# 1-Schematic_Robot_Dog_ESP32_Control_PCB_.net
KiCad netlist of a schematic drawn in EasyEDA
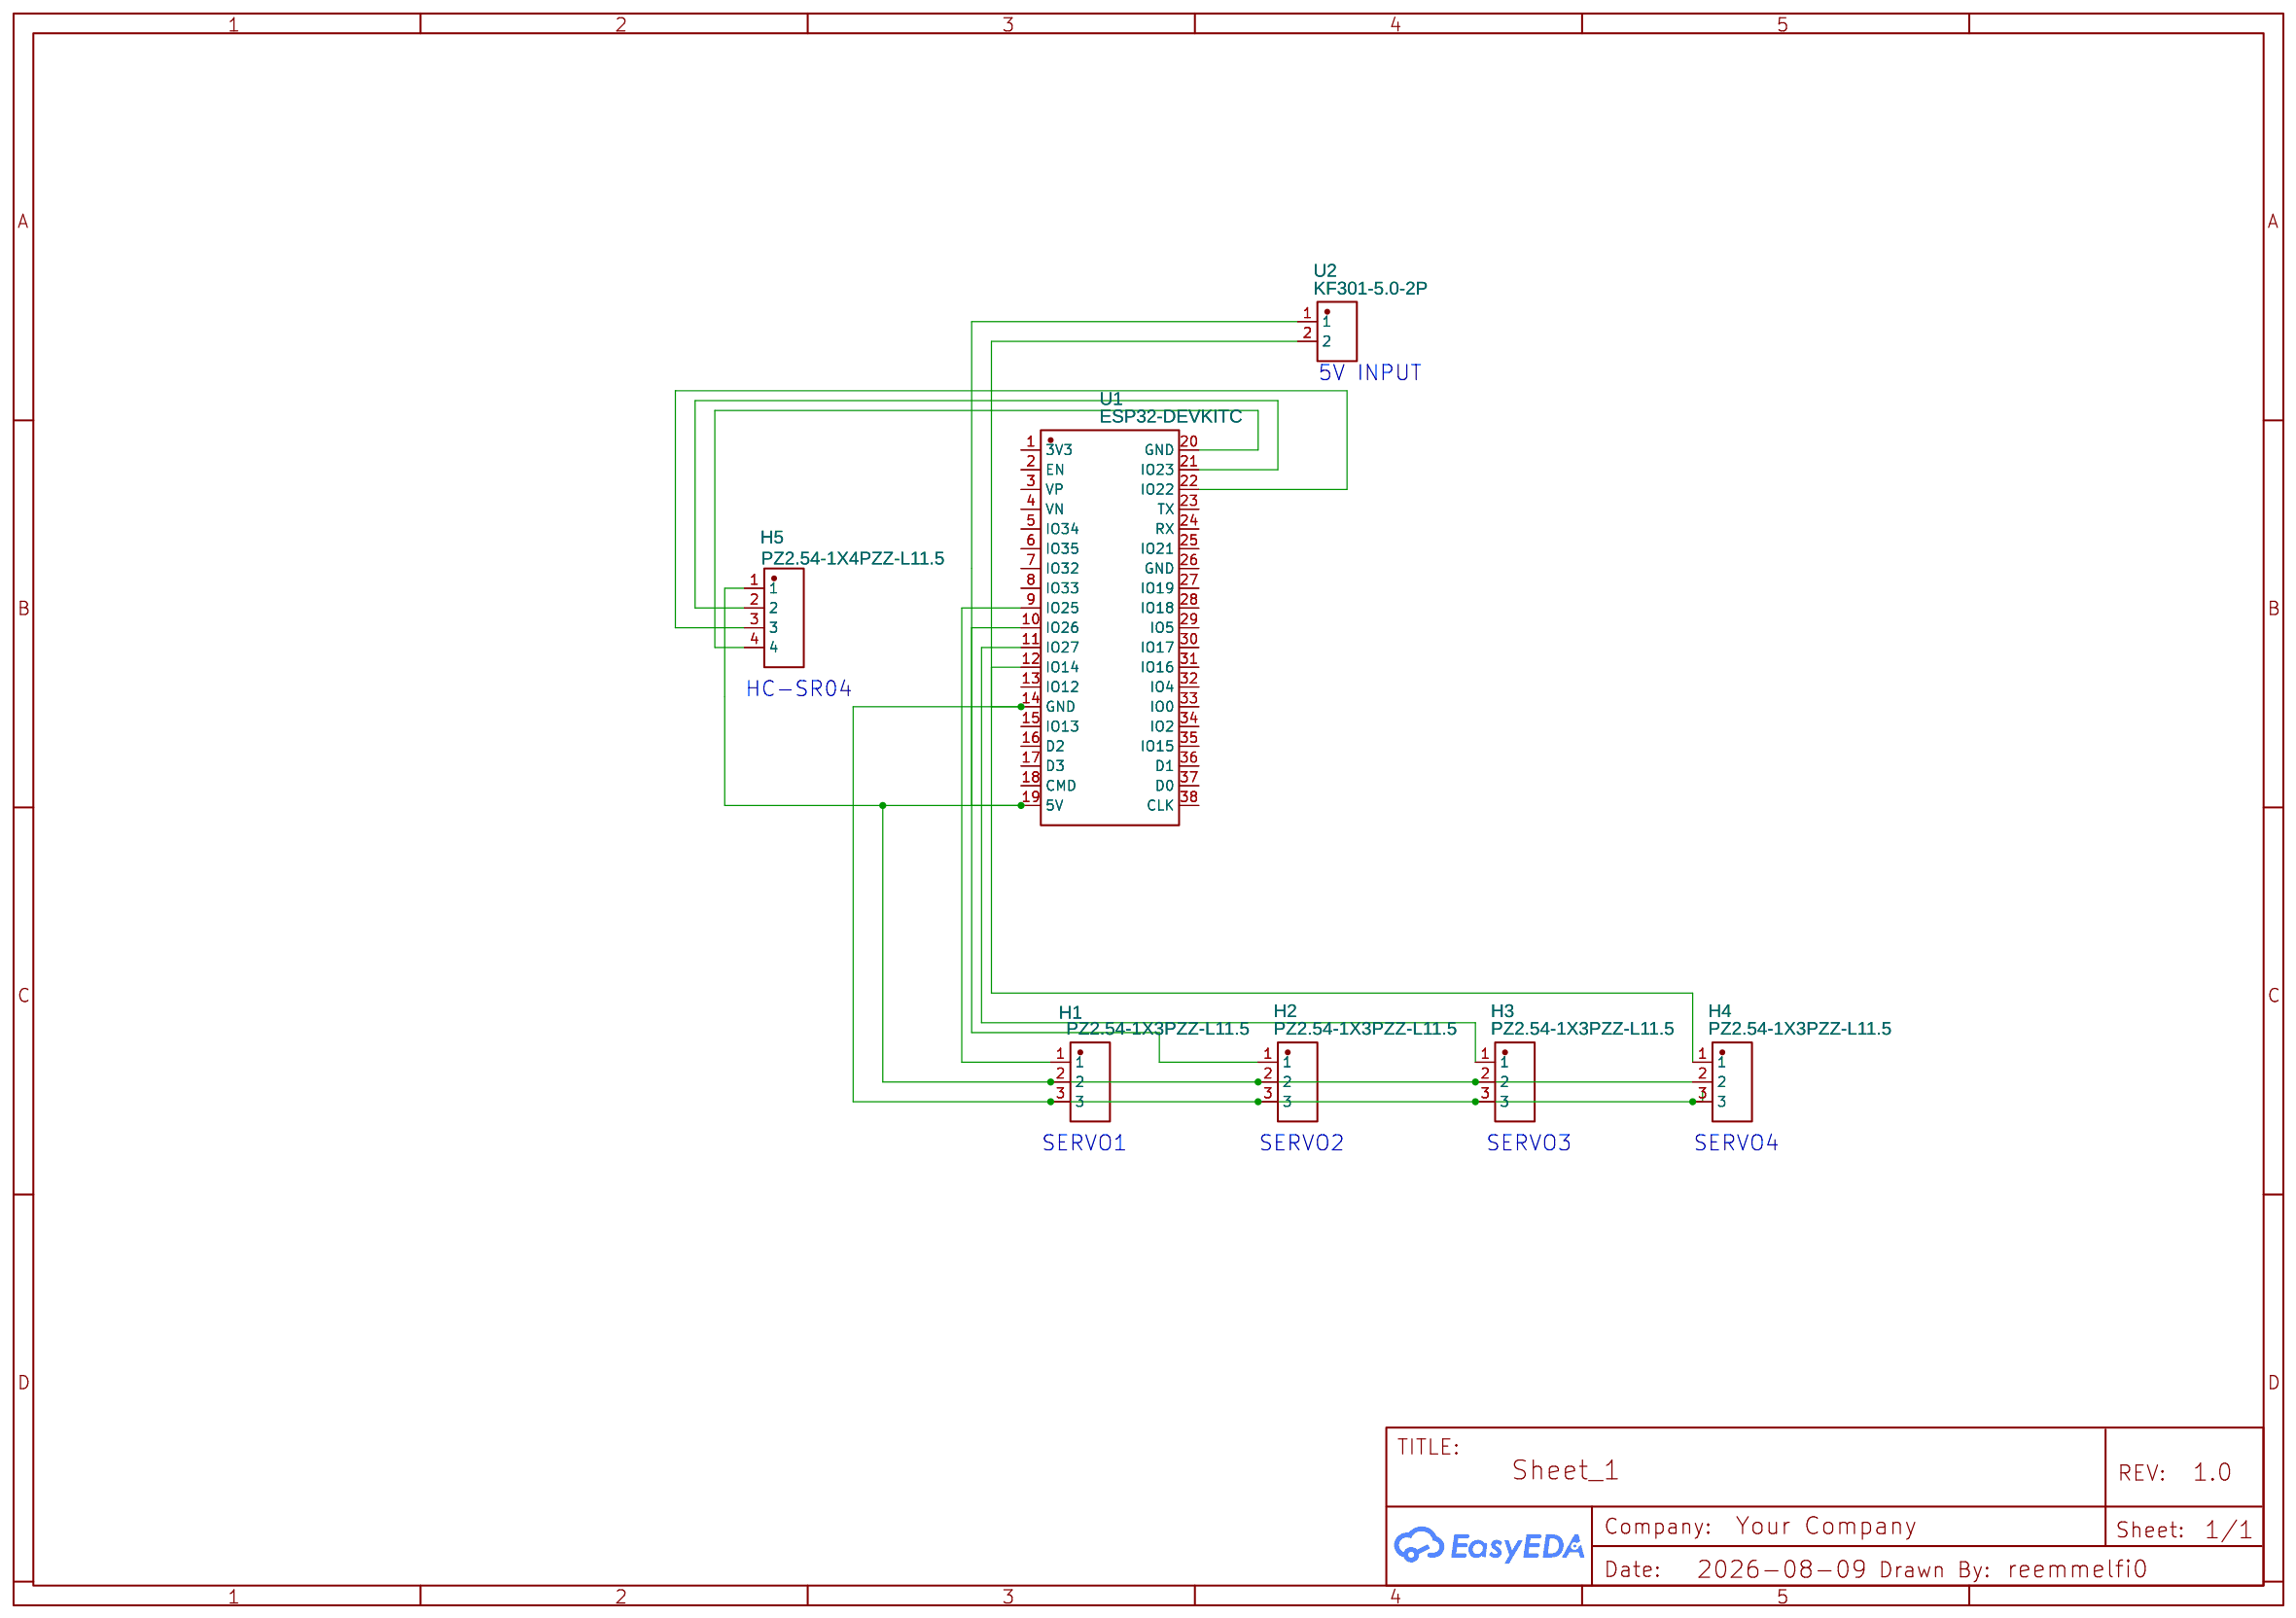
[diagram p0: schematic sheet]

(export (version "E")
  (design (tool "Eeschema 10.0.6"))
  (components
    (comp (ref "H1")
      (value "PZ2.54-1X3PZZ-L11.5")
      (fields
        (field (name "Manufacturer Part") "PZ2.54-1x3PZZ-L11.5")
        (field (name "Manufacturer") "SHOU HAN(首韩)")
      )
      (libsource (lib "") (part "PZ2.54-1X3PZZ-L11.5"))
    )
    (comp (ref "H2")
      (value "PZ2.54-1X3PZZ-L11.5")
      (fields
        (field (name "Manufacturer Part") "PZ2.54-1x3PZZ-L11.5")
        (field (name "Manufacturer") "SHOU HAN(首韩)")
      )
      (libsource (lib "") (part "PZ2.54-1X3PZZ-L11.5"))
    )
    (comp (ref "H3")
      (value "PZ2.54-1X3PZZ-L11.5")
      (fields
        (field (name "Manufacturer Part") "PZ2.54-1x3PZZ-L11.5")
        (field (name "Manufacturer") "SHOU HAN(首韩)")
      )
      (libsource (lib "") (part "PZ2.54-1X3PZZ-L11.5"))
    )
    (comp (ref "H4")
      (value "PZ2.54-1X3PZZ-L11.5")
      (fields
        (field (name "Manufacturer Part") "PZ2.54-1x3PZZ-L11.5")
        (field (name "Manufacturer") "SHOU HAN(首韩)")
      )
      (libsource (lib "") (part "PZ2.54-1X3PZZ-L11.5"))
    )
    (comp (ref "H5")
      (value "PZ2.54-1X4PZZ-L11.5")
      (fields
        (field (name "Manufacturer Part") "PZ2.54-1x4PZZ-L11.5")
        (field (name "Manufacturer") "SHOU HAN(首韩)")
      )
      (libsource (lib "") (part "PZ2.54-1X4PZZ-L11.5"))
    )
    (comp (ref "U1")
      (value "ESP32-DEVKITC")
      (fields
        (field (name "Manufacturer Part") "ESP32-DevKitC")
        (field (name "Manufacturer") "ESPRESSIF(乐鑫)")
      )
      (libsource (lib "") (part "ESP32-DEVKITC"))
    )
    (comp (ref "U2")
      (value "KF301-5.0-2P")
      (fields (field (name "Manufacturer") "KEFA(科发)"))
      (libsource (lib "") (part "KF301-5.0-2P"))
    )
  )
  (nets
    (net (code "1") (name "Net-(H1-Pad3)") (class "Default")
      (node (ref "H1") (pin "3") (pinfunction "3_3") (pintype "unspecified"))
      (node (ref "H2") (pin "3") (pinfunction "3_3") (pintype "unspecified"))
      (node (ref "H3") (pin "3") (pinfunction "3_3") (pintype "unspecified"))
      (node (ref "H4") (pin "3") (pinfunction "3_3") (pintype "unspecified"))
      (node (ref "U1") (pin "14") (pinfunction "GND_14") (pintype "unspecified"))
      (node (ref "U2") (pin "2") (pinfunction "2_2") (pintype "unspecified"))
    )
    (net (code "2") (name "Net-(H5-Pad4)") (class "Default")
      (node (ref "H5") (pin "4") (pinfunction "4_4") (pintype "unspecified"))
      (node (ref "U1") (pin "20") (pinfunction "GND_20") (pintype "unspecified"))
    )
    (net (code "3") (name "Net-(U1-5V)") (class "Default")
      (node (ref "H1") (pin "2") (pinfunction "2_2") (pintype "unspecified"))
      (node (ref "H2") (pin "2") (pinfunction "2_2") (pintype "unspecified"))
      (node (ref "H3") (pin "2") (pinfunction "2_2") (pintype "unspecified"))
      (node (ref "H4") (pin "2") (pinfunction "2_2") (pintype "unspecified"))
      (node (ref "H5") (pin "1") (pinfunction "1_1") (pintype "unspecified"))
      (node (ref "U1") (pin "19") (pinfunction "5V_19") (pintype "unspecified"))
      (node (ref "U2") (pin "1") (pinfunction "1_1") (pintype "unspecified"))
    )
    (net (code "4") (name "Net-(U1-IO14)") (class "Default")
      (node (ref "H4") (pin "1") (pinfunction "1_1") (pintype "unspecified"))
      (node (ref "U1") (pin "12") (pinfunction "IO14_12") (pintype "unspecified"))
    )
    (net (code "5") (name "Net-(U1-IO22)") (class "Default")
      (node (ref "H5") (pin "3") (pinfunction "3_3") (pintype "unspecified"))
      (node (ref "U1") (pin "22") (pinfunction "IO22_22") (pintype "unspecified"))
    )
    (net (code "6") (name "Net-(U1-IO23)") (class "Default")
      (node (ref "H5") (pin "2") (pinfunction "2_2") (pintype "unspecified"))
      (node (ref "U1") (pin "21") (pinfunction "IO23_21") (pintype "unspecified"))
    )
    (net (code "7") (name "Net-(U1-IO25)") (class "Default")
      (node (ref "H1") (pin "1") (pinfunction "1_1") (pintype "unspecified"))
      (node (ref "U1") (pin "9") (pinfunction "IO25_9") (pintype "unspecified"))
    )
    (net (code "8") (name "Net-(U1-IO26)") (class "Default")
      (node (ref "H2") (pin "1") (pinfunction "1_1") (pintype "unspecified"))
      (node (ref "U1") (pin "10") (pinfunction "IO26_10") (pintype "unspecified"))
    )
    (net (code "9") (name "Net-(U1-IO27)") (class "Default")
      (node (ref "H3") (pin "1") (pinfunction "1_1") (pintype "unspecified"))
      (node (ref "U1") (pin "11") (pinfunction "IO27_11") (pintype "unspecified"))
    )
    (net (code "10") (name "unconnected-(U1-3V3-Pad1)") (class "Default")
      (node (ref "U1") (pin "1") (pinfunction "3V3_1") (pintype "unspecified"))
    )
    (net (code "11") (name "unconnected-(U1-CLK-Pad38)") (class "Default")
      (node (ref "U1") (pin "38") (pinfunction "CLK_38") (pintype "unspecified"))
    )
    (net (code "12") (name "unconnected-(U1-CMD-Pad18)") (class "Default")
      (node (ref "U1") (pin "18") (pinfunction "CMD_18") (pintype "unspecified"))
    )
    (net (code "13") (name "unconnected-(U1-D0-Pad37)") (class "Default")
      (node (ref "U1") (pin "37") (pinfunction "D0_37") (pintype "unspecified"))
    )
    (net (code "14") (name "unconnected-(U1-D1-Pad36)") (class "Default")
      (node (ref "U1") (pin "36") (pinfunction "D1_36") (pintype "unspecified"))
    )
    (net (code "15") (name "unconnected-(U1-D2-Pad16)") (class "Default")
      (node (ref "U1") (pin "16") (pinfunction "D2_16") (pintype "unspecified"))
    )
    (net (code "16") (name "unconnected-(U1-D3-Pad17)") (class "Default")
      (node (ref "U1") (pin "17") (pinfunction "D3_17") (pintype "unspecified"))
    )
    (net (code "17") (name "unconnected-(U1-EN-Pad2)") (class "Default")
      (node (ref "U1") (pin "2") (pinfunction "EN_2") (pintype "unspecified"))
    )
    (net (code "18") (name "unconnected-(U1-GND-Pad26)") (class "Default")
      (node (ref "U1") (pin "26") (pinfunction "GND_26") (pintype "unspecified"))
    )
    (net (code "19") (name "unconnected-(U1-IO0-Pad33)") (class "Default")
      (node (ref "U1") (pin "33") (pinfunction "IO0_33") (pintype "unspecified"))
    )
    (net (code "20") (name "unconnected-(U1-IO2-Pad34)") (class "Default")
      (node (ref "U1") (pin "34") (pinfunction "IO2_34") (pintype "unspecified"))
    )
    (net (code "21") (name "unconnected-(U1-IO4-Pad32)") (class "Default")
      (node (ref "U1") (pin "32") (pinfunction "IO4_32") (pintype "unspecified"))
    )
    (net (code "22") (name "unconnected-(U1-IO5-Pad29)") (class "Default")
      (node (ref "U1") (pin "29") (pinfunction "IO5_29") (pintype "unspecified"))
    )
    (net (code "23") (name "unconnected-(U1-IO12-Pad13)") (class "Default")
      (node (ref "U1") (pin "13") (pinfunction "IO12_13") (pintype "unspecified"))
    )
    (net (code "24") (name "unconnected-(U1-IO13-Pad15)") (class "Default")
      (node (ref "U1") (pin "15") (pinfunction "IO13_15") (pintype "unspecified"))
    )
    (net (code "25") (name "unconnected-(U1-IO15-Pad35)") (class "Default")
      (node (ref "U1") (pin "35") (pinfunction "IO15_35") (pintype "unspecified"))
    )
    (net (code "26") (name "unconnected-(U1-IO16-Pad31)") (class "Default")
      (node (ref "U1") (pin "31") (pinfunction "IO16_31") (pintype "unspecified"))
    )
    (net (code "27") (name "unconnected-(U1-IO17-Pad30)") (class "Default")
      (node (ref "U1") (pin "30") (pinfunction "IO17_30") (pintype "unspecified"))
    )
    (net (code "28") (name "unconnected-(U1-IO18-Pad28)") (class "Default")
      (node (ref "U1") (pin "28") (pinfunction "IO18_28") (pintype "unspecified"))
    )
    (net (code "29") (name "unconnected-(U1-IO19-Pad27)") (class "Default")
      (node (ref "U1") (pin "27") (pinfunction "IO19_27") (pintype "unspecified"))
    )
    (net (code "30") (name "unconnected-(U1-IO21-Pad25)") (class "Default")
      (node (ref "U1") (pin "25") (pinfunction "IO21_25") (pintype "unspecified"))
    )
    (net (code "31") (name "unconnected-(U1-IO32-Pad7)") (class "Default")
      (node (ref "U1") (pin "7") (pinfunction "IO32_7") (pintype "unspecified"))
    )
    (net (code "32") (name "unconnected-(U1-IO33-Pad8)") (class "Default")
      (node (ref "U1") (pin "8") (pinfunction "IO33_8") (pintype "unspecified"))
    )
    (net (code "33") (name "unconnected-(U1-IO34-Pad5)") (class "Default")
      (node (ref "U1") (pin "5") (pinfunction "IO34_5") (pintype "unspecified"))
    )
    (net (code "34") (name "unconnected-(U1-IO35-Pad6)") (class "Default")
      (node (ref "U1") (pin "6") (pinfunction "IO35_6") (pintype "unspecified"))
    )
    (net (code "35") (name "unconnected-(U1-RX-Pad24)") (class "Default")
      (node (ref "U1") (pin "24") (pinfunction "RX_24") (pintype "unspecified"))
    )
    (net (code "36") (name "unconnected-(U1-TX-Pad23)") (class "Default")
      (node (ref "U1") (pin "23") (pinfunction "TX_23") (pintype "unspecified"))
    )
    (net (code "37") (name "unconnected-(U1-VN-Pad4)") (class "Default")
      (node (ref "U1") (pin "4") (pinfunction "VN_4") (pintype "unspecified"))
    )
    (net (code "38") (name "unconnected-(U1-VP-Pad3)") (class "Default")
      (node (ref "U1") (pin "3") (pinfunction "VP_3") (pintype "unspecified"))
    )
  )
)
